# fanspeed.net
KiCad netlist of a schematic drawn in EAGLE
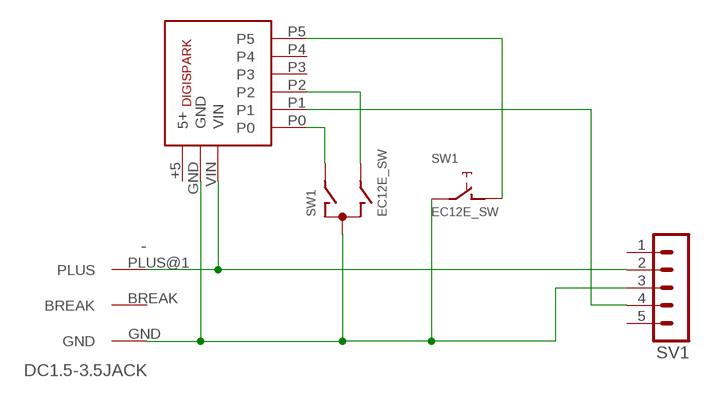
[diagram p0: schematic, sheet 1]

(export (version "E")
  (design (tool "Eeschema 10.0.6"))
  (components
    (comp (ref "-")
      (value "DC1.5-3.5JACK")
      (footprint "eagle-import:DC1.5-3.5JACK")
      (libsource (lib "eagle-import") (part "DC1.5-3.5JACK"))
    )
    (comp (ref "SV1")
      (value "MA05-1")
      (footprint "eagle-import:MA05-1")
      (libsource (lib "eagle-import") (part "MA05-1"))
    )
    (comp (ref "SW1")
      (value "EC12E_SW")
      (footprint "eagle-import:ALPS_EC12E_SW")
      (fields (field (name "MPN") "EC12E2424407"))
      (libsource (lib "eagle-import") (part "EC12E_SW"))
    )
    (comp (ref "U1")
      (value "DIGISPARK")
      (footprint "eagle-import:DISPARK-BOARD")
      (libsource (lib "eagle-import") (part "DIGISPARK"))
    )
  )
  (nets
    (net (code "1") (name "Net-(--PLUS)") (class "Default")
      (node (ref "-") (pin "PLUS@1") (pinfunction "PLUS_PLUS@1") (pintype "bidirectional"))
      (node (ref "SV1") (pin "2") (pinfunction "2_2") (pintype "passive"))
      (node (ref "U1") (pin "VIN") (pinfunction "VIN_VIN") (pintype "bidirectional"))
    )
    (net (code "2") (name "Net-(SV1-Pad4)") (class "Default")
      (node (ref "SV1") (pin "4") (pinfunction "4_4") (pintype "passive"))
      (node (ref "U1") (pin "P1") (pinfunction "P1_P1") (pintype "bidirectional"))
    )
    (net (code "3") (name "Net-(SW1-PadA)") (class "Default")
      (node (ref "SW1") (pin "A") (pinfunction "A_A") (pintype "passive"))
      (node (ref "U1") (pin "P0") (pinfunction "P0_P0") (pintype "bidirectional"))
    )
    (net (code "4") (name "Net-(SW1-PadB)") (class "Default")
      (node (ref "SW1") (pin "B") (pinfunction "B_B") (pintype "passive"))
      (node (ref "U1") (pin "P2") (pinfunction "P2_P2") (pintype "bidirectional"))
    )
    (net (code "5") (name "Net-(SW1B-1)") (class "Default")
      (node (ref "SW1") (pin "D") (pinfunction "1_D") (pintype "passive"))
      (node (ref "U1") (pin "P5") (pinfunction "P5_P5") (pintype "bidirectional"))
    )
    (net (code "6") (name "Net-(SW1B-2)") (class "Default")
      (node (ref "-") (pin "GND") (pinfunction "GND_GND") (pintype "bidirectional"))
      (node (ref "SV1") (pin "3") (pinfunction "3_3") (pintype "passive"))
      (node (ref "SW1") (pin "C") (pinfunction "C_C") (pintype "passive"))
      (node (ref "SW1") (pin "E") (pinfunction "2_E") (pintype "passive"))
      (node (ref "U1") (pin "GND") (pinfunction "GND_GND") (pintype "bidirectional"))
    )
    (net (code "7") (name "unconnected-(--PadBREAK)") (class "Default")
      (node (ref "-") (pin "BREAK") (pinfunction "BREAK_BREAK") (pintype "bidirectional"))
    )
    (net (code "8") (name "unconnected-(SV1-Pad1)") (class "Default")
      (node (ref "SV1") (pin "1") (pinfunction "1_1") (pintype "passive"))
    )
    (net (code "9") (name "unconnected-(SV1-Pad5)") (class "Default")
      (node (ref "SV1") (pin "5") (pinfunction "5_5") (pintype "passive"))
    )
    (net (code "10") (name "unconnected-(U1-5+-Pad+5)") (class "Default")
      (node (ref "U1") (pin "+5") (pinfunction "5+_+5") (pintype "bidirectional"))
    )
    (net (code "11") (name "unconnected-(U1-PadP3)") (class "Default")
      (node (ref "U1") (pin "P3") (pinfunction "P3_P3") (pintype "bidirectional"))
    )
    (net (code "12") (name "unconnected-(U1-PadP4)") (class "Default")
      (node (ref "U1") (pin "P4") (pinfunction "P4_P4") (pintype "bidirectional"))
    )
  )
)
